# Digital_Dice_Schematic.net
KiCad netlist of a schematic drawn in EAGLE
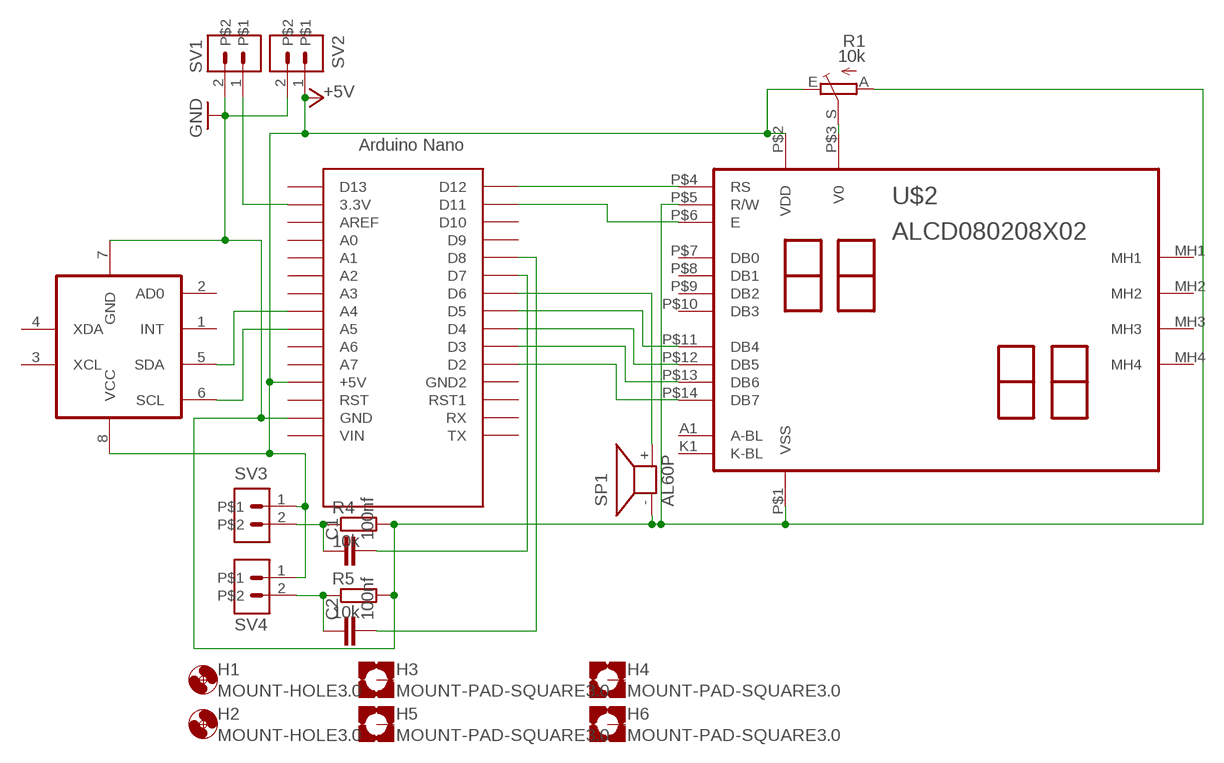
[diagram p0: schematic, sheet 1]

(export (version "E")
  (design (tool "Eeschema 10.0.6"))
  (components
    (comp (ref "C1")
      (value "100nf")
      (footprint "eagle-import:C050-025X075W")
      (libsource (lib "eagle-import") (part "C-EU050-025W"))
    )
    (comp (ref "C2")
      (value "100nf")
      (footprint "eagle-import:C050-025X075W")
      (libsource (lib "eagle-import") (part "C-EU050-025W"))
    )
    (comp (ref "H1")
      (value "MOUNT-HOLE3.0")
      (footprint "eagle-import:3,0")
      (libsource (lib "eagle-import") (part "MOUNT-HOLE3.0"))
    )
    (comp (ref "H2")
      (value "MOUNT-HOLE3.0")
      (footprint "eagle-import:3,0")
      (libsource (lib "eagle-import") (part "MOUNT-HOLE3.0"))
    )
    (comp (ref "H3")
      (value "MOUNT-PAD-SQUARE3.0")
      (footprint "eagle-import:3,0-PAD-SQUARE")
      (libsource (lib "eagle-import") (part "MOUNT-PAD-SQUARE3.0"))
    )
    (comp (ref "H4")
      (value "MOUNT-PAD-SQUARE3.0")
      (footprint "eagle-import:3,0-PAD-SQUARE")
      (libsource (lib "eagle-import") (part "MOUNT-PAD-SQUARE3.0"))
    )
    (comp (ref "H5")
      (value "MOUNT-PAD-SQUARE3.0")
      (footprint "eagle-import:3,0-PAD-SQUARE")
      (libsource (lib "eagle-import") (part "MOUNT-PAD-SQUARE3.0"))
    )
    (comp (ref "H6")
      (value "MOUNT-PAD-SQUARE3.0")
      (footprint "eagle-import:3,0-PAD-SQUARE")
      (libsource (lib "eagle-import") (part "MOUNT-PAD-SQUARE3.0"))
    )
    (comp (ref "R1")
      (value "10k")
      (footprint "eagle-import:CA9V")
      (libsource (lib "eagle-import") (part "TRIM_EU-CA9V"))
    )
    (comp (ref "R4")
      (value "10k")
      (footprint "eagle-import:0207_12")
      (libsource (lib "eagle-import") (part "R-EU_0207/12"))
    )
    (comp (ref "R5")
      (value "10k")
      (footprint "eagle-import:0207_12")
      (libsource (lib "eagle-import") (part "R-EU_0207/12"))
    )
    (comp (ref "SP1")
      (value "AL60P")
      (footprint "eagle-import:AL60P")
      (libsource (lib "eagle-import") (part "AL60P"))
    )
    (comp (ref "SV1")
      (value "MA02-1")
      (footprint "eagle-import:MA02-1")
      (libsource (lib "eagle-import") (part "MA02-1"))
    )
    (comp (ref "SV2")
      (value "MA02-1")
      (footprint "eagle-import:MA02-1")
      (libsource (lib "eagle-import") (part "MA02-1"))
    )
    (comp (ref "SV3")
      (value "MA02-1")
      (footprint "eagle-import:MA02-1")
      (libsource (lib "eagle-import") (part "MA02-1"))
    )
    (comp (ref "SV4")
      (value "MA02-1")
      (footprint "eagle-import:MA02-1")
      (libsource (lib "eagle-import") (part "MA02-1"))
    )
    (comp (ref "U$1")
      (value "NANO")
      (footprint "eagle-import:NANO")
      (libsource (lib "eagle-import") (part "NANO"))
    )
    (comp (ref "U$2")
      (value "ALCD080208X02")
      (footprint "eagle-import:ALCD0802")
      (libsource (lib "eagle-import") (part "ALCD080208X02"))
    )
    (comp (ref "X1")
      (value "GYRO_MPU-6050")
      (footprint "eagle-import:MPU")
      (libsource (lib "eagle-import") (part "GYRO_MPU-6050"))
    )
  )
  (nets
    (net (code "1") (name "+5V") (class "Default")
      (node (ref "R1") (pin "E") (pinfunction "E_E") (pintype "passive"))
      (node (ref "SV2") (pin "1") (pinfunction "P$1_1") (pintype "passive"))
      (node (ref "SV3") (pin "1") (pinfunction "P$1_1") (pintype "passive"))
      (node (ref "SV4") (pin "1") (pinfunction "P$1_1") (pintype "passive"))
      (node (ref "U$1") (pin "5V") (pinfunction "+5V_5V") (pintype "bidirectional"))
      (node (ref "U$2") (pin "P$2") (pinfunction "VDD_P$2") (pintype "bidirectional"))
      (node (ref "X1") (pin "8") (pinfunction "VCC_8") (pintype "bidirectional"))
    )
    (net (code "2") (name "GND") (class "Default")
      (node (ref "R1") (pin "A") (pinfunction "A_A") (pintype "passive"))
      (node (ref "R4") (pin "2") (pinfunction "2_2") (pintype "passive"))
      (node (ref "R5") (pin "2") (pinfunction "2_2") (pintype "passive"))
      (node (ref "SP1") (pin "-") (pinfunction "1_-") (pintype "passive"))
      (node (ref "SV1") (pin "2") (pinfunction "P$2_2") (pintype "passive"))
      (node (ref "SV2") (pin "2") (pinfunction "P$2_2") (pintype "passive"))
      (node (ref "U$1") (pin "GND") (pinfunction "GND_GND") (pintype "bidirectional"))
      (node (ref "U$2") (pin "P$1") (pinfunction "VSS_P$1") (pintype "bidirectional"))
      (node (ref "U$2") (pin "P$5") (pinfunction "R/W_P$5") (pintype "bidirectional"))
      (node (ref "X1") (pin "7") (pinfunction "GND_7") (pintype "bidirectional"))
    )
    (net (code "3") (name "Net-(C1-Pad2)") (class "Default")
      (node (ref "C1") (pin "2") (pinfunction "2_2") (pintype "passive"))
      (node (ref "U$1") (pin "D7") (pinfunction "D7_D7") (pintype "bidirectional"))
    )
    (net (code "4") (name "Net-(C2-Pad2)") (class "Default")
      (node (ref "C2") (pin "2") (pinfunction "2_2") (pintype "passive"))
      (node (ref "U$1") (pin "D8") (pinfunction "D8_D8") (pintype "bidirectional"))
    )
    (net (code "5") (name "Net-(SP1-2)") (class "Default")
      (node (ref "SP1") (pin "+") (pinfunction "2_+") (pintype "passive"))
      (node (ref "U$1") (pin "D6") (pinfunction "D6_D6") (pintype "bidirectional"))
    )
    (net (code "6") (name "Net-(SV1-P$1)") (class "Default")
      (node (ref "SV1") (pin "1") (pinfunction "P$1_1") (pintype "passive"))
      (node (ref "U$1") (pin "3.3V") (pinfunction "3.3V_3.3V") (pintype "bidirectional"))
    )
    (net (code "7") (name "Net-(SV3-P$2)") (class "Default")
      (node (ref "C1") (pin "1") (pinfunction "1_1") (pintype "passive"))
      (node (ref "R4") (pin "1") (pinfunction "1_1") (pintype "passive"))
      (node (ref "SV3") (pin "2") (pinfunction "P$2_2") (pintype "passive"))
    )
    (net (code "8") (name "Net-(SV4-P$2)") (class "Default")
      (node (ref "C2") (pin "1") (pinfunction "1_1") (pintype "passive"))
      (node (ref "R5") (pin "1") (pinfunction "1_1") (pintype "passive"))
      (node (ref "SV4") (pin "2") (pinfunction "P$2_2") (pintype "passive"))
    )
    (net (code "9") (name "Net-(U$2-DB4)") (class "Default")
      (node (ref "U$1") (pin "D5") (pinfunction "D5_D5") (pintype "bidirectional"))
      (node (ref "U$2") (pin "P$11") (pinfunction "DB4_P$11") (pintype "bidirectional"))
    )
    (net (code "10") (name "Net-(U$2-DB5)") (class "Default")
      (node (ref "U$1") (pin "D4") (pinfunction "D4_D4") (pintype "bidirectional"))
      (node (ref "U$2") (pin "P$12") (pinfunction "DB5_P$12") (pintype "bidirectional"))
    )
    (net (code "11") (name "Net-(U$2-DB6)") (class "Default")
      (node (ref "U$1") (pin "D3") (pinfunction "D3_D3") (pintype "bidirectional"))
      (node (ref "U$2") (pin "P$13") (pinfunction "DB6_P$13") (pintype "bidirectional"))
    )
    (net (code "12") (name "Net-(U$2-DB7)") (class "Default")
      (node (ref "U$1") (pin "D2") (pinfunction "D2_D2") (pintype "bidirectional"))
      (node (ref "U$2") (pin "P$14") (pinfunction "DB7_P$14") (pintype "bidirectional"))
    )
    (net (code "13") (name "Net-(U$2-E)") (class "Default")
      (node (ref "U$1") (pin "D11") (pinfunction "D11_D11") (pintype "bidirectional"))
      (node (ref "U$2") (pin "P$6") (pinfunction "E_P$6") (pintype "bidirectional"))
    )
    (net (code "14") (name "Net-(U$2-RS)") (class "Default")
      (node (ref "U$1") (pin "D12") (pinfunction "D12_D12") (pintype "bidirectional"))
      (node (ref "U$2") (pin "P$4") (pinfunction "RS_P$4") (pintype "bidirectional"))
    )
    (net (code "15") (name "Net-(U$2-V0)") (class "Default")
      (node (ref "R1") (pin "S") (pinfunction "S_S") (pintype "passive"))
      (node (ref "U$2") (pin "P$3") (pinfunction "V0_P$3") (pintype "bidirectional"))
    )
    (net (code "16") (name "Net-(X1-SCL)") (class "Default")
      (node (ref "U$1") (pin "A5") (pinfunction "A5_A5") (pintype "bidirectional"))
      (node (ref "X1") (pin "6") (pinfunction "SCL_6") (pintype "bidirectional"))
    )
    (net (code "17") (name "Net-(X1-SDA)") (class "Default")
      (node (ref "U$1") (pin "A4") (pinfunction "A4_A4") (pintype "bidirectional"))
      (node (ref "X1") (pin "5") (pinfunction "SDA_5") (pintype "bidirectional"))
    )
    (net (code "18") (name "unconnected-(H3-MOUNT-PadB3,0)") (class "Default")
      (node (ref "H3") (pin "B3,0") (pinfunction "MOUNT_B3,0") (pintype "passive"))
    )
    (net (code "19") (name "unconnected-(H4-MOUNT-PadB3,0)") (class "Default")
      (node (ref "H4") (pin "B3,0") (pinfunction "MOUNT_B3,0") (pintype "passive"))
    )
    (net (code "20") (name "unconnected-(H5-MOUNT-PadB3,0)") (class "Default")
      (node (ref "H5") (pin "B3,0") (pinfunction "MOUNT_B3,0") (pintype "passive"))
    )
    (net (code "21") (name "unconnected-(H6-MOUNT-PadB3,0)") (class "Default")
      (node (ref "H6") (pin "B3,0") (pinfunction "MOUNT_B3,0") (pintype "passive"))
    )
    (net (code "22") (name "unconnected-(U$1-GND2-PadGND1)") (class "Default")
      (node (ref "U$1") (pin "GND1") (pinfunction "GND2_GND1") (pintype "bidirectional"))
    )
    (net (code "23") (name "unconnected-(U$1-PadA0)") (class "Default")
      (node (ref "U$1") (pin "A0") (pinfunction "A0_A0") (pintype "bidirectional"))
    )
    (net (code "24") (name "unconnected-(U$1-PadA1)") (class "Default")
      (node (ref "U$1") (pin "A1") (pinfunction "A1_A1") (pintype "bidirectional"))
    )
    (net (code "25") (name "unconnected-(U$1-PadA2)") (class "Default")
      (node (ref "U$1") (pin "A2") (pinfunction "A2_A2") (pintype "bidirectional"))
    )
    (net (code "26") (name "unconnected-(U$1-PadA3)") (class "Default")
      (node (ref "U$1") (pin "A3") (pinfunction "A3_A3") (pintype "bidirectional"))
    )
    (net (code "27") (name "unconnected-(U$1-PadA6)") (class "Default")
      (node (ref "U$1") (pin "A6") (pinfunction "A6_A6") (pintype "bidirectional"))
    )
    (net (code "28") (name "unconnected-(U$1-PadA7)") (class "Default")
      (node (ref "U$1") (pin "A7") (pinfunction "A7_A7") (pintype "bidirectional"))
    )
    (net (code "29") (name "unconnected-(U$1-PadAREF)") (class "Default")
      (node (ref "U$1") (pin "AREF") (pinfunction "AREF_AREF") (pintype "bidirectional"))
    )
    (net (code "30") (name "unconnected-(U$1-PadD9)") (class "Default")
      (node (ref "U$1") (pin "D9") (pinfunction "D9_D9") (pintype "bidirectional"))
    )
    (net (code "31") (name "unconnected-(U$1-PadD10)") (class "Default")
      (node (ref "U$1") (pin "D10") (pinfunction "D10_D10") (pintype "bidirectional"))
    )
    (net (code "32") (name "unconnected-(U$1-PadD13)") (class "Default")
      (node (ref "U$1") (pin "D13") (pinfunction "D13_D13") (pintype "bidirectional"))
    )
    (net (code "33") (name "unconnected-(U$1-PadICSP1)") (class "Default")
      (node (ref "U$1") (pin "ICSP1") (pinfunction "ICSP1_ICSP1") (pintype "bidirectional"))
    )
    (net (code "34") (name "unconnected-(U$1-PadICSP2)") (class "Default")
      (node (ref "U$1") (pin "ICSP2") (pinfunction "ICSP2_ICSP2") (pintype "bidirectional"))
    )
    (net (code "35") (name "unconnected-(U$1-PadICSP3)") (class "Default")
      (node (ref "U$1") (pin "ICSP3") (pinfunction "ICSP3_ICSP3") (pintype "bidirectional"))
    )
    (net (code "36") (name "unconnected-(U$1-PadICSP4)") (class "Default")
      (node (ref "U$1") (pin "ICSP4") (pinfunction "ICSP4_ICSP4") (pintype "bidirectional"))
    )
    (net (code "37") (name "unconnected-(U$1-PadICSP5)") (class "Default")
      (node (ref "U$1") (pin "ICSP5") (pinfunction "ICSP5_ICSP5") (pintype "bidirectional"))
    )
    (net (code "38") (name "unconnected-(U$1-PadICSP6)") (class "Default")
      (node (ref "U$1") (pin "ICSP6") (pinfunction "ICSP6_ICSP6") (pintype "bidirectional"))
    )
    (net (code "39") (name "unconnected-(U$1-PadRST)") (class "Default")
      (node (ref "U$1") (pin "RST") (pinfunction "RST_RST") (pintype "bidirectional"))
    )
    (net (code "40") (name "unconnected-(U$1-PadRST1)") (class "Default")
      (node (ref "U$1") (pin "RST1") (pinfunction "RST1_RST1") (pintype "bidirectional"))
    )
    (net (code "41") (name "unconnected-(U$1-RX-PadRX1)") (class "Default")
      (node (ref "U$1") (pin "RX1") (pinfunction "RX_RX1") (pintype "bidirectional"))
    )
    (net (code "42") (name "unconnected-(U$1-TX-PadTX0)") (class "Default")
      (node (ref "U$1") (pin "TX0") (pinfunction "TX_TX0") (pintype "bidirectional"))
    )
    (net (code "43") (name "unconnected-(U$1-VIN-PadRAW)") (class "Default")
      (node (ref "U$1") (pin "RAW") (pinfunction "VIN_RAW") (pintype "bidirectional"))
    )
    (net (code "44") (name "unconnected-(U$2-A-BL-PadA1)") (class "Default")
      (node (ref "U$2") (pin "A1") (pinfunction "A-BL_A1") (pintype "bidirectional"))
    )
    (net (code "45") (name "unconnected-(U$2-DB0-PadP$7)") (class "Default")
      (node (ref "U$2") (pin "P$7") (pinfunction "DB0_P$7") (pintype "bidirectional"))
    )
    (net (code "46") (name "unconnected-(U$2-DB1-PadP$8)") (class "Default")
      (node (ref "U$2") (pin "P$8") (pinfunction "DB1_P$8") (pintype "bidirectional"))
    )
    (net (code "47") (name "unconnected-(U$2-DB2-PadP$9)") (class "Default")
      (node (ref "U$2") (pin "P$9") (pinfunction "DB2_P$9") (pintype "bidirectional"))
    )
    (net (code "48") (name "unconnected-(U$2-DB3-PadP$10)") (class "Default")
      (node (ref "U$2") (pin "P$10") (pinfunction "DB3_P$10") (pintype "bidirectional"))
    )
    (net (code "49") (name "unconnected-(U$2-K-BL-PadK1)") (class "Default")
      (node (ref "U$2") (pin "K1") (pinfunction "K-BL_K1") (pintype "bidirectional"))
    )
    (net (code "50") (name "unconnected-(U$2-PadMH1)") (class "Default")
      (node (ref "U$2") (pin "MH1") (pinfunction "MH1_MH1") (pintype "bidirectional"))
    )
    (net (code "51") (name "unconnected-(U$2-PadMH2)") (class "Default")
      (node (ref "U$2") (pin "MH2") (pinfunction "MH2_MH2") (pintype "bidirectional"))
    )
    (net (code "52") (name "unconnected-(U$2-PadMH3)") (class "Default")
      (node (ref "U$2") (pin "MH3") (pinfunction "MH3_MH3") (pintype "bidirectional"))
    )
    (net (code "53") (name "unconnected-(U$2-PadMH4)") (class "Default")
      (node (ref "U$2") (pin "MH4") (pinfunction "MH4_MH4") (pintype "bidirectional"))
    )
    (net (code "54") (name "unconnected-(X1-AD0-Pad2)") (class "Default")
      (node (ref "X1") (pin "2") (pinfunction "AD0_2") (pintype "bidirectional"))
    )
    (net (code "55") (name "unconnected-(X1-INT-Pad1)") (class "Default")
      (node (ref "X1") (pin "1") (pinfunction "INT_1") (pintype "bidirectional"))
    )
    (net (code "56") (name "unconnected-(X1-XCL-Pad3)") (class "Default")
      (node (ref "X1") (pin "3") (pinfunction "XCL_3") (pintype "bidirectional"))
    )
    (net (code "57") (name "unconnected-(X1-XDA-Pad4)") (class "Default")
      (node (ref "X1") (pin "4") (pinfunction "XDA_4") (pintype "bidirectional"))
    )
  )
)
